# NAME_of_the_Game__Arduino_AND_Gate_Emula.net
KiCad netlist of a schematic drawn in EAGLE
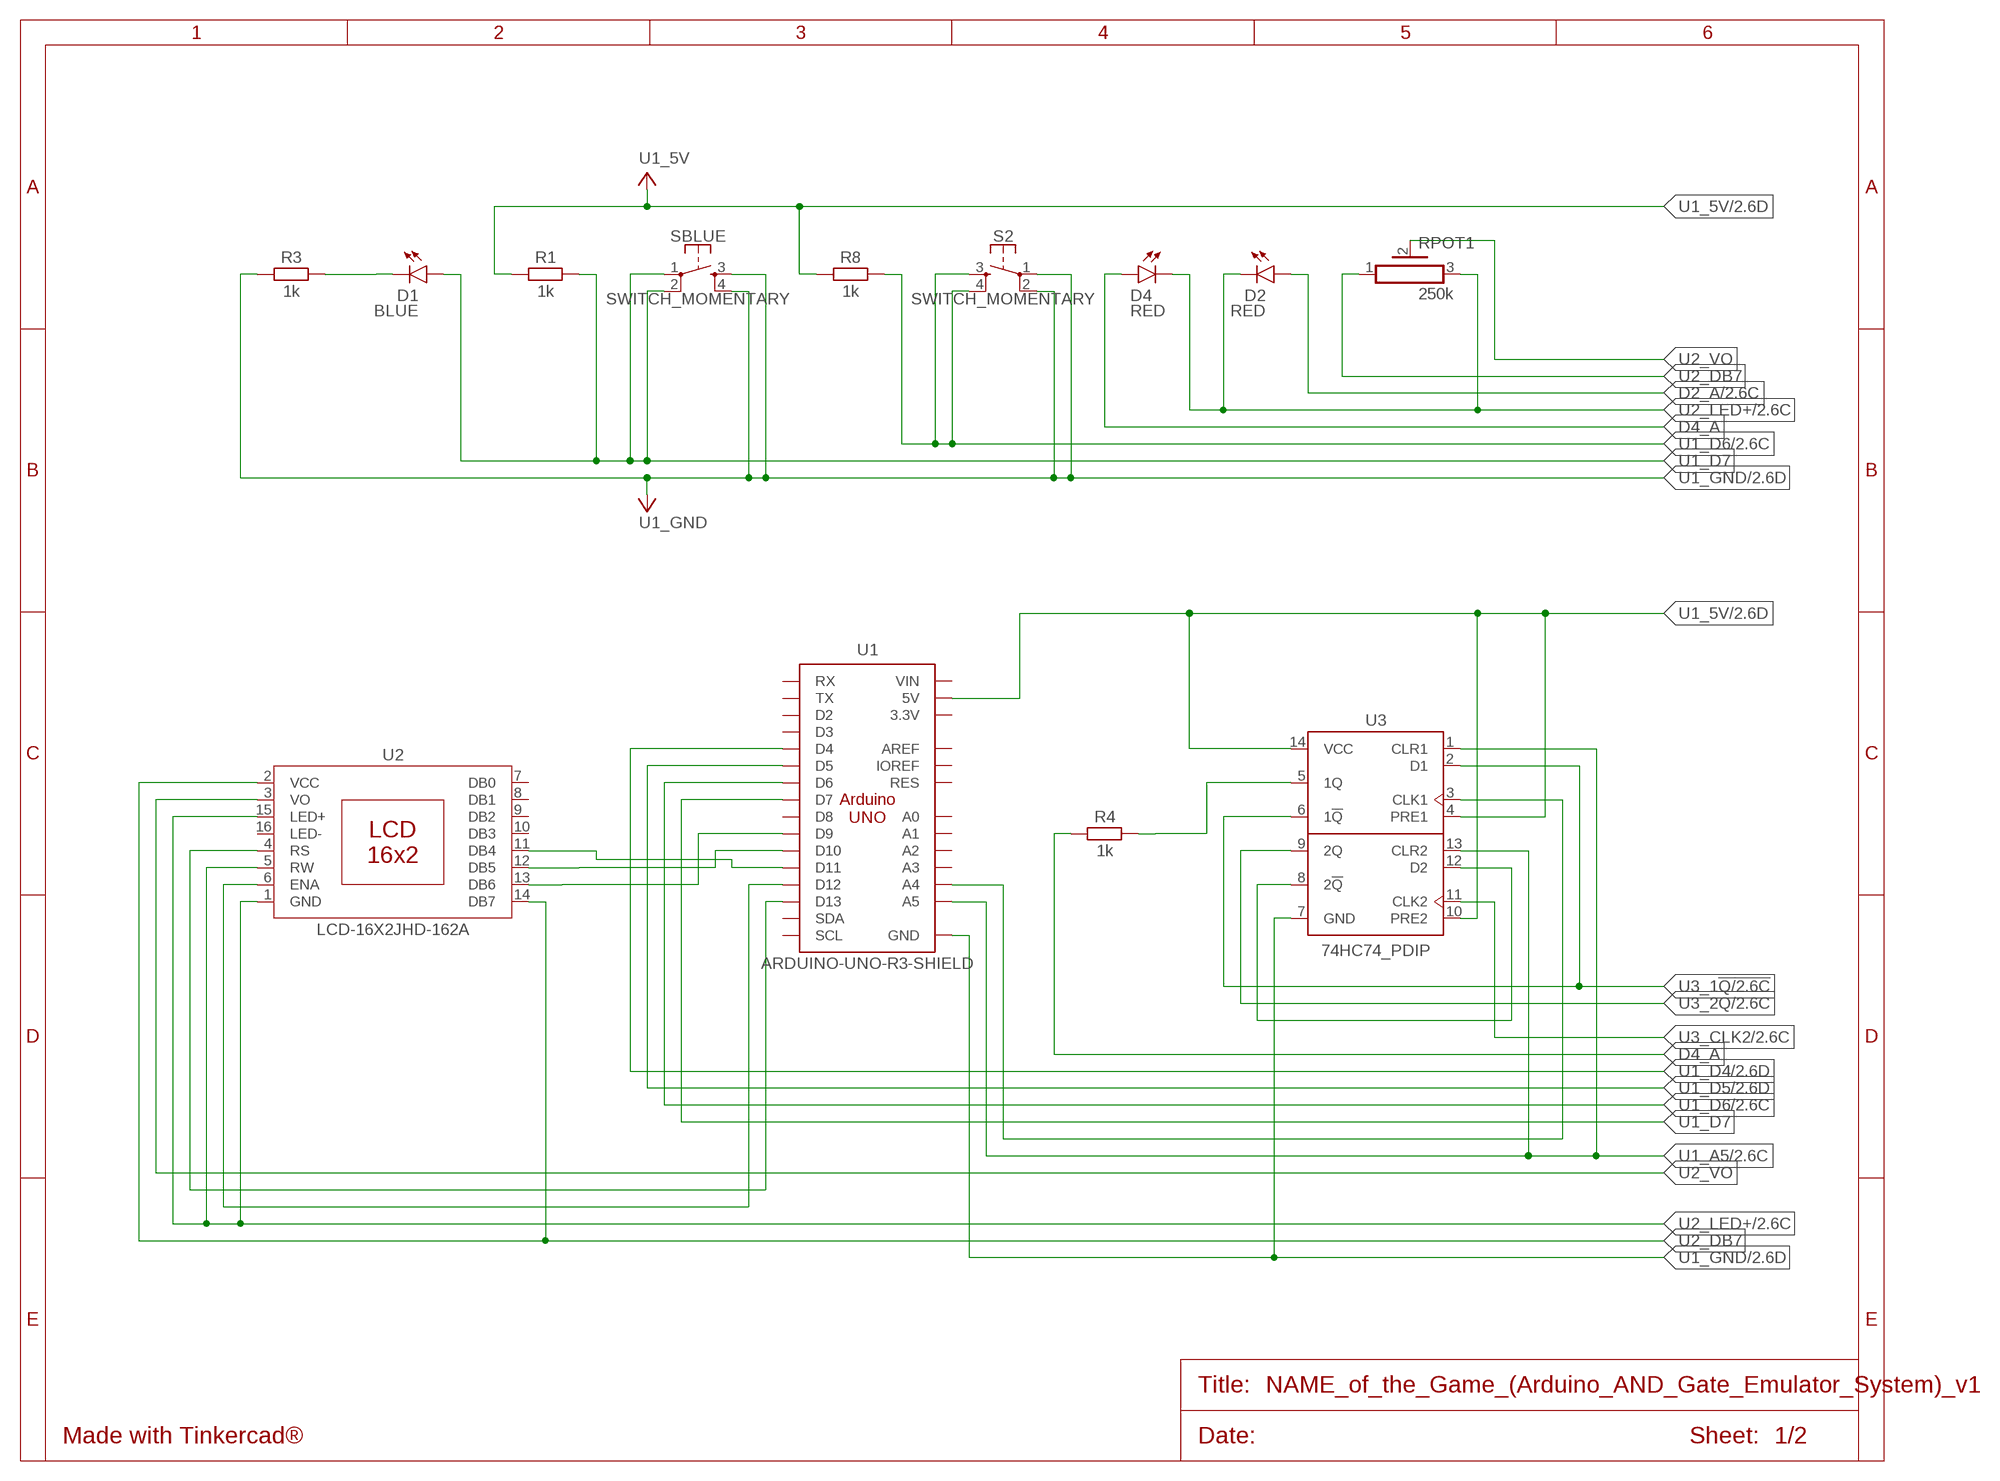
[diagram p0: schematic, sheet 1]
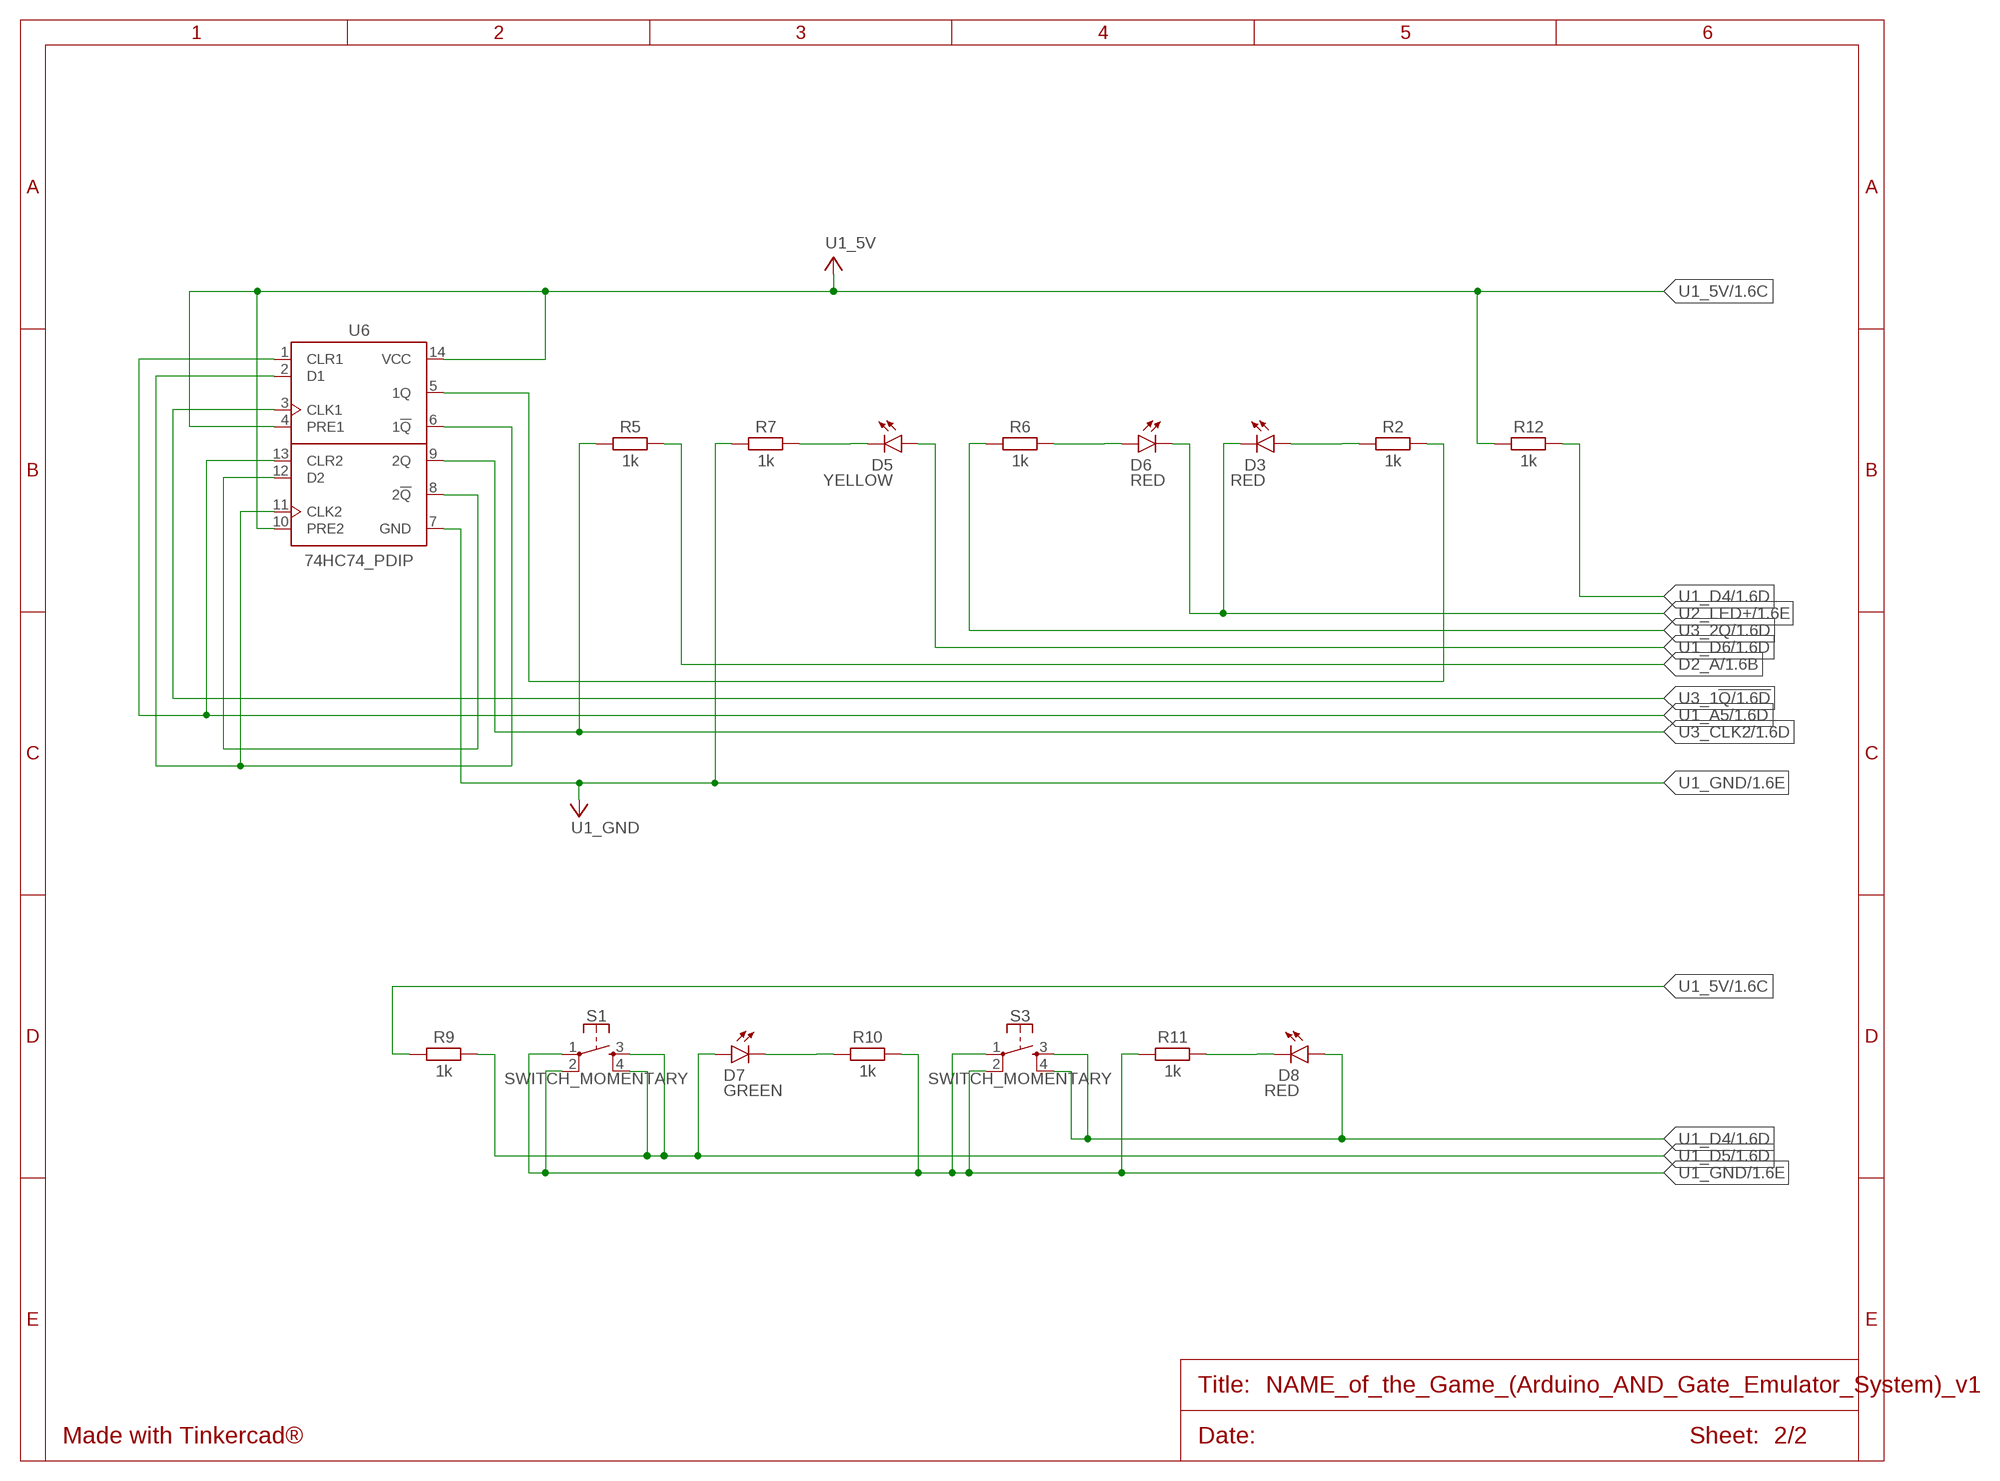
[diagram p1: schematic, sheet 2]

(export (version "E")
  (design (tool "Eeschema 10.0.6"))
  (components
    (comp (ref "D1")
      (value "BLUE")
      (footprint "eagle-import:LEDRD254W60D565H860B_B")
      (libsource (lib "eagle-import") (part "LED_RADIALBLUE_"))
    )
    (comp (ref "D2")
      (value "RED")
      (footprint "eagle-import:LEDRD254W60D565H860B")
      (libsource (lib "eagle-import") (part "LED_RADIALRED_"))
    )
    (comp (ref "D4")
      (value "RED")
      (footprint "eagle-import:LEDRD254W60D565H860B")
      (libsource (lib "eagle-import") (part "LED_RADIALRED_"))
    )
    (comp (ref "R1")
      (value "1k")
      (footprint "eagle-import:RESAD1016W63L850D250B")
      (libsource (lib "eagle-import") (part "RESISTOR_AXIAL-10.16MM-PITCH"))
    )
    (comp (ref "R3")
      (value "1k")
      (footprint "eagle-import:RESAD1016W63L850D250B")
      (libsource (lib "eagle-import") (part "RESISTOR_AXIAL-10.16MM-PITCH"))
    )
    (comp (ref "R4")
      (value "1k")
      (footprint "eagle-import:RESAD1016W63L850D250B")
      (libsource (lib "eagle-import") (part "RESISTOR_AXIAL-10.16MM-PITCH"))
    )
    (comp (ref "R8")
      (value "1k")
      (footprint "eagle-import:RESAD1016W63L850D250B")
      (libsource (lib "eagle-import") (part "RESISTOR_AXIAL-10.16MM-PITCH"))
    )
    (comp (ref "RPOT1")
      (value "250k")
      (footprint "eagle-import:HA-06-SM065")
      (libsource (lib "eagle-import") (part "POT_HA-06"))
    )
    (comp (ref "S2")
      (value "SWITCH_MOMENTARY")
      (footprint "eagle-import:SWITCH-MOMENTARY-PTH-6.5MM")
      (libsource (lib "eagle-import") (part "SWITCH_MOMENTARY"))
    )
    (comp (ref "SBLUE")
      (value "SWITCH_MOMENTARY")
      (footprint "eagle-import:SWITCH-MOMENTARY-PTH-6.5MM")
      (libsource (lib "eagle-import") (part "SWITCH_MOMENTARY"))
    )
    (comp (ref "U1")
      (value "ARDUINO-UNO-R3-SHIELD")
      (footprint "eagle-import:ARDUINO-UNO-R3-SHIELD")
      (libsource (lib "eagle-import") (part "ARDUINO-UNO-R3-SHIELD"))
    )
    (comp (ref "U2")
      (value "LCD-16X2JHD-162A")
      (footprint "eagle-import:JHD-162A")
      (libsource (lib "eagle-import") (part "LCD-16X2JHD-162A"))
    )
    (comp (ref "U3")
      (value "74HC74_PDIP")
      (footprint "eagle-import:DIP762W53P254L1969H508Q14B")
      (libsource (lib "eagle-import") (part "74HC74_PDIP"))
    )
    (comp (ref "D3")
      (value "RED")
      (footprint "eagle-import:LEDRD254W60D565H860B")
      (libsource (lib "eagle-import") (part "LED_RADIALRED_"))
    )
    (comp (ref "D5")
      (value "YELLOW")
      (footprint "eagle-import:LEDRD254W60D565H860B_Y")
      (libsource (lib "eagle-import") (part "LED_RADIALYELLOW_"))
    )
    (comp (ref "D6")
      (value "RED")
      (footprint "eagle-import:LEDRD254W60D565H860B")
      (libsource (lib "eagle-import") (part "LED_RADIALRED_"))
    )
    (comp (ref "D7")
      (value "GREEN")
      (footprint "eagle-import:LEDRD254W60D565H860B_G")
      (libsource (lib "eagle-import") (part "LED_RADIALGREEN_"))
    )
    (comp (ref "D8")
      (value "RED")
      (footprint "eagle-import:LEDRD254W60D565H860B")
      (libsource (lib "eagle-import") (part "LED_RADIALRED_"))
    )
    (comp (ref "R2")
      (value "1k")
      (footprint "eagle-import:RESAD1016W63L850D250B")
      (libsource (lib "eagle-import") (part "RESISTOR_AXIAL-10.16MM-PITCH"))
    )
    (comp (ref "R5")
      (value "1k")
      (footprint "eagle-import:RESAD1016W63L850D250B")
      (libsource (lib "eagle-import") (part "RESISTOR_AXIAL-10.16MM-PITCH"))
    )
    (comp (ref "R6")
      (value "1k")
      (footprint "eagle-import:RESAD1016W63L850D250B")
      (libsource (lib "eagle-import") (part "RESISTOR_AXIAL-10.16MM-PITCH"))
    )
    (comp (ref "R7")
      (value "1k")
      (footprint "eagle-import:RESAD1016W63L850D250B")
      (libsource (lib "eagle-import") (part "RESISTOR_AXIAL-10.16MM-PITCH"))
    )
    (comp (ref "R9")
      (value "1k")
      (footprint "eagle-import:RESAD1016W63L850D250B")
      (libsource (lib "eagle-import") (part "RESISTOR_AXIAL-10.16MM-PITCH"))
    )
    (comp (ref "R10")
      (value "1k")
      (footprint "eagle-import:RESAD1016W63L850D250B")
      (libsource (lib "eagle-import") (part "RESISTOR_AXIAL-10.16MM-PITCH"))
    )
    (comp (ref "R11")
      (value "1k")
      (footprint "eagle-import:RESAD1016W63L850D250B")
      (libsource (lib "eagle-import") (part "RESISTOR_AXIAL-10.16MM-PITCH"))
    )
    (comp (ref "R12")
      (value "1k")
      (footprint "eagle-import:RESAD1016W63L850D250B")
      (libsource (lib "eagle-import") (part "RESISTOR_AXIAL-10.16MM-PITCH"))
    )
    (comp (ref "S1")
      (value "SWITCH_MOMENTARY")
      (footprint "eagle-import:SWITCH-MOMENTARY-PTH-6.5MM")
      (libsource (lib "eagle-import") (part "SWITCH_MOMENTARY"))
    )
    (comp (ref "S3")
      (value "SWITCH_MOMENTARY")
      (footprint "eagle-import:SWITCH-MOMENTARY-PTH-6.5MM")
      (libsource (lib "eagle-import") (part "SWITCH_MOMENTARY"))
    )
    (comp (ref "U6")
      (value "74HC74_PDIP")
      (footprint "eagle-import:DIP762W53P254L1969H508Q14B")
      (libsource (lib "eagle-import") (part "74HC74_PDIP"))
    )
  )
  (nets
    (net (code "1") (name "D2_A") (class "Default")
      (node (ref "D2") (pin "1") (pinfunction "A_1") (pintype "passive"))
      (node (ref "R5") (pin "2") (pinfunction "2_2") (pintype "passive"))
    )
    (net (code "2") (name "D4_A") (class "Default")
      (node (ref "D4") (pin "1") (pinfunction "A_1") (pintype "passive"))
      (node (ref "R4") (pin "2") (pinfunction "2_2") (pintype "passive"))
    )
    (net (code "3") (name "Net-(D1-C)") (class "Default")
      (node (ref "D1") (pin "2") (pinfunction "C_2") (pintype "passive"))
      (node (ref "R3") (pin "1") (pinfunction "1_1") (pintype "passive"))
    )
    (net (code "4") (name "Net-(D3-A)") (class "Default")
      (node (ref "D3") (pin "1") (pinfunction "A_1") (pintype "passive"))
      (node (ref "R2") (pin "2") (pinfunction "2_2") (pintype "passive"))
    )
    (net (code "5") (name "Net-(D5-C)") (class "Default")
      (node (ref "D5") (pin "2") (pinfunction "C_2") (pintype "passive"))
      (node (ref "R7") (pin "1") (pinfunction "1_1") (pintype "passive"))
    )
    (net (code "6") (name "Net-(D6-A)") (class "Default")
      (node (ref "D6") (pin "1") (pinfunction "A_1") (pintype "passive"))
      (node (ref "R6") (pin "2") (pinfunction "2_2") (pintype "passive"))
    )
    (net (code "7") (name "Net-(D7-C)") (class "Default")
      (node (ref "D7") (pin "2") (pinfunction "C_2") (pintype "passive"))
      (node (ref "R10") (pin "1") (pinfunction "1_1") (pintype "passive"))
    )
    (net (code "8") (name "Net-(D8-C)") (class "Default")
      (node (ref "D8") (pin "2") (pinfunction "C_2") (pintype "passive"))
      (node (ref "R11") (pin "1") (pinfunction "1_1") (pintype "passive"))
    )
    (net (code "9") (name "Net-(U2-DB4)") (class "Default")
      (node (ref "U1") (pin "D11") (pinfunction "D11_D11") (pintype "bidirectional"))
      (node (ref "U2") (pin "11") (pinfunction "DB4_11") (pintype "bidirectional"))
    )
    (net (code "10") (name "Net-(U2-DB5)") (class "Default")
      (node (ref "U1") (pin "D10") (pinfunction "D10_D10") (pintype "bidirectional"))
      (node (ref "U2") (pin "12") (pinfunction "DB5_12") (pintype "bidirectional"))
    )
    (net (code "11") (name "Net-(U2-DB6)") (class "Default")
      (node (ref "U1") (pin "D9") (pinfunction "D9_D9") (pintype "bidirectional"))
      (node (ref "U2") (pin "13") (pinfunction "DB6_13") (pintype "bidirectional"))
    )
    (net (code "12") (name "Net-(U2-ENA)") (class "Default")
      (node (ref "U1") (pin "D12") (pinfunction "D12_D12") (pintype "bidirectional"))
      (node (ref "U2") (pin "6") (pinfunction "ENA_6") (pintype "bidirectional"))
    )
    (net (code "13") (name "Net-(U2-RS)") (class "Default")
      (node (ref "U1") (pin "D13") (pinfunction "D13_D13") (pintype "bidirectional"))
      (node (ref "U2") (pin "4") (pinfunction "RS_4") (pintype "bidirectional"))
    )
    (net (code "14") (name "Net-(U3-1Q)") (class "Default")
      (node (ref "R4") (pin "1") (pinfunction "1_1") (pintype "passive"))
      (node (ref "U3") (pin "5") (pinfunction "1Q_5") (pintype "output"))
    )
    (net (code "15") (name "Net-(U3-2~{Q})") (class "Default")
      (node (ref "U3") (pin "12") (pinfunction "D2_12") (pintype "input"))
      (node (ref "U3") (pin "8") (pinfunction "2~{Q}_8") (pintype "output"))
    )
    (net (code "16") (name "Net-(U3-CLK1)") (class "Default")
      (node (ref "U1") (pin "A4") (pinfunction "A4_A4") (pintype "bidirectional"))
      (node (ref "U3") (pin "3") (pinfunction "CLK1_3") (pintype "input"))
    )
    (net (code "17") (name "Net-(U6-1Q)") (class "Default")
      (node (ref "R2") (pin "1") (pinfunction "1_1") (pintype "passive"))
      (node (ref "U6") (pin "5") (pinfunction "1Q_5") (pintype "output"))
    )
    (net (code "18") (name "Net-(U6-1~{Q})") (class "Default")
      (node (ref "U6") (pin "11") (pinfunction "CLK2_11") (pintype "input"))
      (node (ref "U6") (pin "2") (pinfunction "D1_2") (pintype "input"))
      (node (ref "U6") (pin "6") (pinfunction "1~{Q}_6") (pintype "output"))
    )
    (net (code "19") (name "Net-(U6-2~{Q})") (class "Default")
      (node (ref "U6") (pin "12") (pinfunction "D2_12") (pintype "input"))
      (node (ref "U6") (pin "8") (pinfunction "2~{Q}_8") (pintype "output"))
    )
    (net (code "20") (name "U1_5V") (class "Default")
      (node (ref "R1") (pin "1") (pinfunction "1_1") (pintype "passive"))
      (node (ref "R12") (pin "1") (pinfunction "1_1") (pintype "passive"))
      (node (ref "R8") (pin "1") (pinfunction "1_1") (pintype "passive"))
      (node (ref "R9") (pin "1") (pinfunction "1_1") (pintype "passive"))
      (node (ref "U1") (pin "5V") (pinfunction "5V_5V") (pintype "bidirectional"))
      (node (ref "U3") (pin "10") (pinfunction "PRE2_10") (pintype "input"))
      (node (ref "U3") (pin "14") (pinfunction "VCC_14") (pintype "bidirectional"))
      (node (ref "U3") (pin "4") (pinfunction "PRE1_4") (pintype "input"))
      (node (ref "U6") (pin "10") (pinfunction "PRE2_10") (pintype "input"))
      (node (ref "U6") (pin "14") (pinfunction "VCC_14") (pintype "bidirectional"))
      (node (ref "U6") (pin "4") (pinfunction "PRE1_4") (pintype "input"))
    )
    (net (code "21") (name "U1_A5") (class "Default")
      (node (ref "U1") (pin "A5") (pinfunction "A5_A5") (pintype "bidirectional"))
      (node (ref "U3") (pin "1") (pinfunction "CLR1_1") (pintype "input"))
      (node (ref "U3") (pin "13") (pinfunction "CLR2_13") (pintype "input"))
      (node (ref "U6") (pin "1") (pinfunction "CLR1_1") (pintype "input"))
      (node (ref "U6") (pin "13") (pinfunction "CLR2_13") (pintype "input"))
    )
    (net (code "22") (name "U1_D4") (class "Default")
      (node (ref "D8") (pin "1") (pinfunction "A_1") (pintype "passive"))
      (node (ref "R12") (pin "2") (pinfunction "2_2") (pintype "passive"))
      (node (ref "S3") (pin "3") (pinfunction "3_3") (pintype "passive"))
      (node (ref "S3") (pin "4") (pinfunction "4_4") (pintype "passive"))
      (node (ref "U1") (pin "D4") (pinfunction "D4_D4") (pintype "bidirectional"))
    )
    (net (code "23") (name "U1_D5") (class "Default")
      (node (ref "D7") (pin "1") (pinfunction "A_1") (pintype "passive"))
      (node (ref "R9") (pin "2") (pinfunction "2_2") (pintype "passive"))
      (node (ref "S1") (pin "3") (pinfunction "3_3") (pintype "passive"))
      (node (ref "S1") (pin "4") (pinfunction "4_4") (pintype "passive"))
      (node (ref "U1") (pin "D5") (pinfunction "D5_D5") (pintype "bidirectional"))
    )
    (net (code "24") (name "U1_D6") (class "Default")
      (node (ref "D5") (pin "1") (pinfunction "A_1") (pintype "passive"))
      (node (ref "R8") (pin "2") (pinfunction "2_2") (pintype "passive"))
      (node (ref "S2") (pin "3") (pinfunction "3_3") (pintype "passive"))
      (node (ref "S2") (pin "4") (pinfunction "4_4") (pintype "passive"))
      (node (ref "U1") (pin "D6") (pinfunction "D6_D6") (pintype "bidirectional"))
    )
    (net (code "25") (name "U1_D7") (class "Default")
      (node (ref "D1") (pin "1") (pinfunction "A_1") (pintype "passive"))
      (node (ref "R1") (pin "2") (pinfunction "2_2") (pintype "passive"))
      (node (ref "SBLUE") (pin "1") (pinfunction "1_1") (pintype "passive"))
      (node (ref "SBLUE") (pin "2") (pinfunction "2_2") (pintype "passive"))
      (node (ref "U1") (pin "D7") (pinfunction "D7_D7") (pintype "bidirectional"))
    )
    (net (code "26") (name "U1_GND") (class "Default")
      (node (ref "R10") (pin "2") (pinfunction "2_2") (pintype "passive"))
      (node (ref "R11") (pin "2") (pinfunction "2_2") (pintype "passive"))
      (node (ref "R3") (pin "2") (pinfunction "2_2") (pintype "passive"))
      (node (ref "R7") (pin "2") (pinfunction "2_2") (pintype "passive"))
      (node (ref "S1") (pin "1") (pinfunction "1_1") (pintype "passive"))
      (node (ref "S1") (pin "2") (pinfunction "2_2") (pintype "passive"))
      (node (ref "S2") (pin "1") (pinfunction "1_1") (pintype "passive"))
      (node (ref "S2") (pin "2") (pinfunction "2_2") (pintype "passive"))
      (node (ref "S3") (pin "1") (pinfunction "1_1") (pintype "passive"))
      (node (ref "S3") (pin "2") (pinfunction "2_2") (pintype "passive"))
      (node (ref "SBLUE") (pin "3") (pinfunction "3_3") (pintype "passive"))
      (node (ref "SBLUE") (pin "4") (pinfunction "4_4") (pintype "passive"))
      (node (ref "U1") (pin "GND@0") (pinfunction "GND_GND@0") (pintype "bidirectional"))
      (node (ref "U1") (pin "GND@1") (pinfunction "GND_GND@1") (pintype "bidirectional"))
      (node (ref "U1") (pin "GND@2") (pinfunction "GND_GND@2") (pintype "bidirectional"))
      (node (ref "U3") (pin "7") (pinfunction "GND_7") (pintype "bidirectional"))
      (node (ref "U6") (pin "7") (pinfunction "GND_7") (pintype "bidirectional"))
    )
    (net (code "27") (name "U2_DB7") (class "Default")
      (node (ref "RPOT1") (pin "1") (pinfunction "P$1_1") (pintype "passive"))
      (node (ref "U2") (pin "14") (pinfunction "DB7_14") (pintype "bidirectional"))
      (node (ref "U2") (pin "2") (pinfunction "VCC_2") (pintype "bidirectional"))
    )
    (net (code "28") (name "U2_LED+") (class "Default")
      (node (ref "D2") (pin "2") (pinfunction "C_2") (pintype "passive"))
      (node (ref "D3") (pin "2") (pinfunction "C_2") (pintype "passive"))
      (node (ref "D4") (pin "2") (pinfunction "C_2") (pintype "passive"))
      (node (ref "D6") (pin "2") (pinfunction "C_2") (pintype "passive"))
      (node (ref "RPOT1") (pin "3") (pinfunction "P$3_3") (pintype "passive"))
      (node (ref "U2") (pin "1") (pinfunction "GND_1") (pintype "bidirectional"))
      (node (ref "U2") (pin "15") (pinfunction "LED+_15") (pintype "bidirectional"))
      (node (ref "U2") (pin "5") (pinfunction "RW_5") (pintype "bidirectional"))
    )
    (net (code "29") (name "U2_VO") (class "Default")
      (node (ref "RPOT1") (pin "2") (pinfunction "P$2_2") (pintype "passive"))
      (node (ref "U2") (pin "3") (pinfunction "VO_3") (pintype "bidirectional"))
    )
    (net (code "30") (name "U3_1~{Q}") (class "Default")
      (node (ref "U3") (pin "2") (pinfunction "D1_2") (pintype "input"))
      (node (ref "U3") (pin "6") (pinfunction "1~{Q}_6") (pintype "output"))
      (node (ref "U6") (pin "3") (pinfunction "CLK1_3") (pintype "input"))
    )
    (net (code "31") (name "U3_2Q") (class "Default")
      (node (ref "R6") (pin "1") (pinfunction "1_1") (pintype "passive"))
      (node (ref "U3") (pin "9") (pinfunction "2Q_9") (pintype "output"))
    )
    (net (code "32") (name "U3_CLK2") (class "Default")
      (node (ref "R5") (pin "1") (pinfunction "1_1") (pintype "passive"))
      (node (ref "U3") (pin "11") (pinfunction "CLK2_11") (pintype "input"))
      (node (ref "U6") (pin "9") (pinfunction "2Q_9") (pintype "output"))
    )
    (net (code "33") (name "unconnected-(U1-Pad3.3V)") (class "Default")
      (node (ref "U1") (pin "3.3V") (pinfunction "3.3V_3.3V") (pintype "bidirectional"))
    )
    (net (code "34") (name "unconnected-(U1-PadA0)") (class "Default")
      (node (ref "U1") (pin "A0") (pinfunction "A0_A0") (pintype "bidirectional"))
    )
    (net (code "35") (name "unconnected-(U1-PadA1)") (class "Default")
      (node (ref "U1") (pin "A1") (pinfunction "A1_A1") (pintype "bidirectional"))
    )
    (net (code "36") (name "unconnected-(U1-PadA2)") (class "Default")
      (node (ref "U1") (pin "A2") (pinfunction "A2_A2") (pintype "bidirectional"))
    )
    (net (code "37") (name "unconnected-(U1-PadA3)") (class "Default")
      (node (ref "U1") (pin "A3") (pinfunction "A3_A3") (pintype "bidirectional"))
    )
    (net (code "38") (name "unconnected-(U1-PadAREF)") (class "Default")
      (node (ref "U1") (pin "AREF") (pinfunction "AREF_AREF") (pintype "bidirectional"))
    )
    (net (code "39") (name "unconnected-(U1-PadD2)") (class "Default")
      (node (ref "U1") (pin "D2") (pinfunction "D2_D2") (pintype "bidirectional"))
    )
    (net (code "40") (name "unconnected-(U1-PadD3)") (class "Default")
      (node (ref "U1") (pin "D3") (pinfunction "D3_D3") (pintype "bidirectional"))
    )
    (net (code "41") (name "unconnected-(U1-PadD8)") (class "Default")
      (node (ref "U1") (pin "D8") (pinfunction "D8_D8") (pintype "bidirectional"))
    )
    (net (code "42") (name "unconnected-(U1-PadIOREF)") (class "Default")
      (node (ref "U1") (pin "IOREF") (pinfunction "IOREF_IOREF") (pintype "bidirectional"))
    )
    (net (code "43") (name "unconnected-(U1-PadRES)") (class "Default")
      (node (ref "U1") (pin "RES") (pinfunction "RES_RES") (pintype "bidirectional"))
    )
    (net (code "44") (name "unconnected-(U1-PadRX)") (class "Default")
      (node (ref "U1") (pin "RX") (pinfunction "RX_RX") (pintype "bidirectional"))
    )
    (net (code "45") (name "unconnected-(U1-PadSCL)") (class "Default")
      (node (ref "U1") (pin "SCL") (pinfunction "SCL_SCL") (pintype "bidirectional"))
    )
    (net (code "46") (name "unconnected-(U1-PadSDA)") (class "Default")
      (node (ref "U1") (pin "SDA") (pinfunction "SDA_SDA") (pintype "bidirectional"))
    )
    (net (code "47") (name "unconnected-(U1-PadTX)") (class "Default")
      (node (ref "U1") (pin "TX") (pinfunction "TX_TX") (pintype "bidirectional"))
    )
    (net (code "48") (name "unconnected-(U1-PadVIN)") (class "Default")
      (node (ref "U1") (pin "VIN") (pinfunction "VIN_VIN") (pintype "bidirectional"))
    )
    (net (code "49") (name "unconnected-(U2-DB0-Pad7)") (class "Default")
      (node (ref "U2") (pin "7") (pinfunction "DB0_7") (pintype "bidirectional"))
    )
    (net (code "50") (name "unconnected-(U2-DB1-Pad8)") (class "Default")
      (node (ref "U2") (pin "8") (pinfunction "DB1_8") (pintype "bidirectional"))
    )
    (net (code "51") (name "unconnected-(U2-DB2-Pad9)") (class "Default")
      (node (ref "U2") (pin "9") (pinfunction "DB2_9") (pintype "bidirectional"))
    )
    (net (code "52") (name "unconnected-(U2-DB3-Pad10)") (class "Default")
      (node (ref "U2") (pin "10") (pinfunction "DB3_10") (pintype "bidirectional"))
    )
    (net (code "53") (name "unconnected-(U2-LED--Pad16)") (class "Default")
      (node (ref "U2") (pin "16") (pinfunction "LED-_16") (pintype "bidirectional"))
    )
  )
)
